# Schematic.net
KiCad netlist of a schematic drawn in Altium Designer
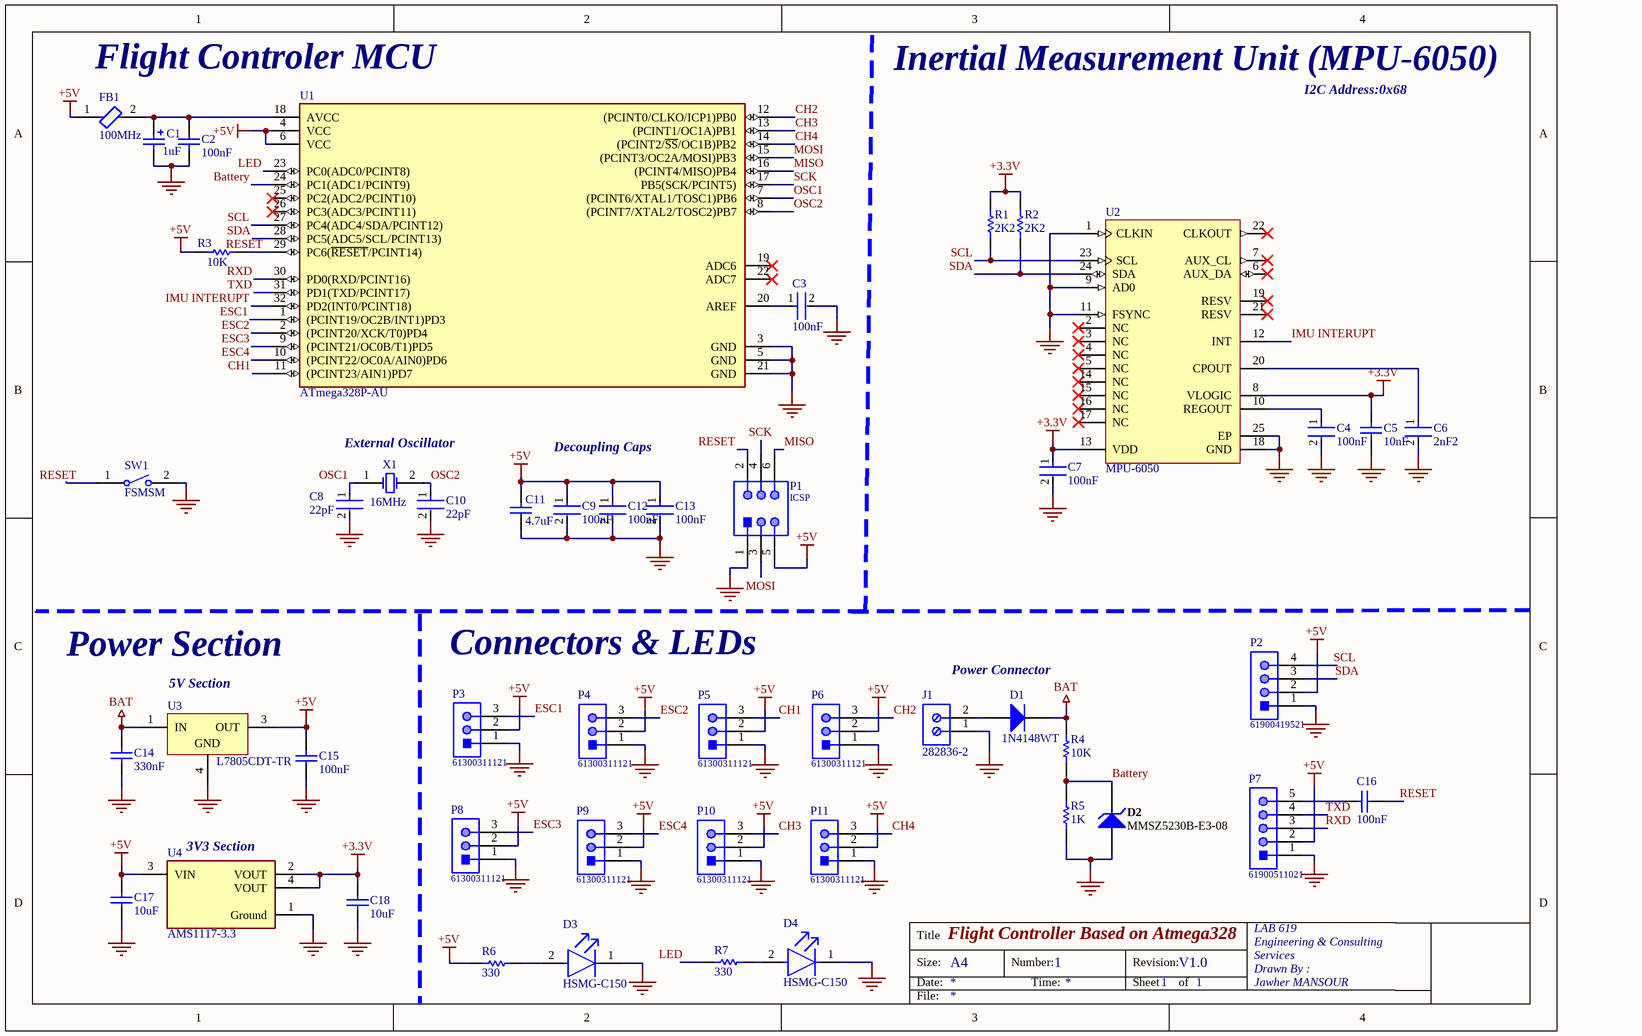
[diagram p0: Schematic.SchDoc]

(export (version "E")
  (design (tool "Eeschema 10.0.6"))
  (components
    (comp (ref "C1")
      (value "1uF")
      (footprint "C1206")
      (description "Polarized Capacitor (Axial)")
      (fields (field (name "PUBLISHER") "Altium Limited"))
      (libsource (lib "Miscellaneous Devices") (part "Cap Pol2"))
    )
    (comp (ref "C2")
      (value "100nF")
      (footprint "CAPC3216X95X55NL15T25")
      (description "Chip Capacitor, 0.1 uF, +/- 10%, 50 V, -55 to 125 degC, 1206 (3216 Metric), RoHS, Tape and Reel")
      (fields (field (name "MANUFACTURER") "Murata"))
      (libsource (lib "Altium Content Vault") (part "CAP-NP-2"))
    )
    (comp (ref "C3")
      (value "100nF")
      (footprint "FP-GRM21B-0_15-MFG")
      (description "Chip Multilayer Ceramic Capacitors for General Purpose, 0805, 22uF, X5R, 15%, 20%, 6.3V")
      (fields (field (name "VOLTAGE") "6.3V") (field (name "TOLERANCE") "20%"))
      (libsource (lib "Altium Content Vault") (part "b4654b650e69147ec39a6b967a45e02"))
    )
    (comp (ref "C4")
      (value "100nF")
      (footprint "FP-GRM188-0_1-e0_2_0_5-IPC_B")
      (description "Chip Multilayer Ceramic Capacitors for General Purpose, 0603, 0.10uF, X7R, 15%, 10%, 100V")
      (fields (field (name "VOLTAGE") "100V") (field (name "TOLERANCE") "10%"))
      (libsource (lib "Altium Content Vault") (part "11868f565c42a9108669ba33697ecf6"))
    )
    (comp (ref "C5")
      (value "10nF")
      (footprint "CAPC1608X90X35ML15T15")
      (fields
        (field (name "MANUFACTURER") "AVX Interconnect / Elco")
        (field (name "PART NUMBER") "0603ZC103MAT2A")
      )
      (libsource (lib "Altium Content Vault") (part "CAP"))
    )
    (comp (ref "C6")
      (value "2nF2")
      (footprint "FP-C0603C-CF-MFG")
      (description "CAP CER 2200PF 100V NP0 0603")
      (fields
        (field (name "OCTOPART") "https://octopart.com/c0603c222f1gactu-kemet-16902737")
        (field (name "MANUFACTURER PART NUMBER") "C0603C222F1GACTU")
      )
      (libsource (lib "Altium Content Vault") (part "b4654b650e69147ec39a6b967a45e02"))
    )
    (comp (ref "C7")
      (value "100nF")
      (footprint "FP-GRM188-0_1-e0_2_0_5-IPC_B")
      (description "Chip Multilayer Ceramic Capacitors for General Purpose, 0603, 0.10uF, X7R, 15%, 10%, 100V")
      (fields (field (name "VOLTAGE") "100V") (field (name "TOLERANCE") "10%"))
      (libsource (lib "Altium Content Vault") (part "11868f565c42a9108669ba33697ecf6"))
    )
    (comp (ref "C8")
      (value "22pF")
      (footprint "FP-C1206C-EB-MFG")
      (description "CAP CER 22PF 100V 5% NP0 1206")
      (fields
        (field (name "MANUFACTURER PART NUMBER") "C1206C220J1GACTU")
        (field (name "MANUFACTURER") "KEMET")
      )
      (libsource (lib "Altium Content Vault") (part "b4654b650e69147ec39a6b967a45e02"))
    )
    (comp (ref "C9")
      (value "100nF")
      (footprint "FP-GRM21B-0_15-MFG")
      (description "Chip Multilayer Ceramic Capacitors for General Purpose, 0805, 22uF, X5R, 15%, 20%, 6.3V")
      (fields (field (name "VOLTAGE") "6.3V") (field (name "TOLERANCE") "20%"))
      (libsource (lib "Altium Content Vault") (part "b4654b650e69147ec39a6b967a45e02"))
    )
    (comp (ref "C10")
      (value "22pF")
      (footprint "FP-C1206C-EB-MFG")
      (description "CAP CER 22PF 100V 5% NP0 1206")
      (fields
        (field (name "MANUFACTURER PART NUMBER") "C1206C220J1GACTU")
        (field (name "MANUFACTURER") "KEMET")
      )
      (libsource (lib "Altium Content Vault") (part "b4654b650e69147ec39a6b967a45e02"))
    )
    (comp (ref "C11")
      (value "4.7uF")
      (footprint "CAPC3216X95X55NL15T25")
      (description "Chip Capacitor, 0.1 uF, +/- 10%, 50 V, -55 to 125 degC, 1206 (3216 Metric), RoHS, Tape and Reel")
      (fields (field (name "MANUFACTURER") "Murata"))
      (libsource (lib "Altium Content Vault") (part "CAP-NP-2"))
    )
    (comp (ref "C12")
      (value "100nF")
      (footprint "FP-GRM21B-0_15-MFG")
      (description "Chip Multilayer Ceramic Capacitors for General Purpose, 0805, 22uF, X5R, 15%, 20%, 6.3V")
      (fields (field (name "VOLTAGE") "6.3V") (field (name "TOLERANCE") "20%"))
      (libsource (lib "Altium Content Vault") (part "b4654b650e69147ec39a6b967a45e02"))
    )
    (comp (ref "C13")
      (value "100nF")
      (footprint "FP-GRM21B-0_15-MFG")
      (description "Chip Multilayer Ceramic Capacitors for General Purpose, 0805, 22uF, X5R, 15%, 20%, 6.3V")
      (fields (field (name "VOLTAGE") "6.3V") (field (name "TOLERANCE") "20%"))
      (libsource (lib "Altium Content Vault") (part "b4654b650e69147ec39a6b967a45e02"))
    )
    (comp (ref "C14")
      (value "330nF")
      (footprint "CAPC3216X95X55NL15T25")
      (description "Chip Capacitor, 0.1 uF, +/- 10%, 50 V, -55 to 125 degC, 1206 (3216 Metric), RoHS, Tape and Reel")
      (fields (field (name "MANUFACTURER") "Murata"))
      (libsource (lib "Altium Content Vault") (part "CAP-NP-2"))
    )
    (comp (ref "C15")
      (value "100nF")
      (footprint "CAPC3216X95X55NL15T25")
      (description "Chip Capacitor, 0.1 uF, +/- 10%, 50 V, -55 to 125 degC, 1206 (3216 Metric), RoHS, Tape and Reel")
      (fields (field (name "MANUFACTURER") "Murata"))
      (libsource (lib "Altium Content Vault") (part "CAP-NP-2"))
    )
    (comp (ref "C16")
      (value "100nF")
      (footprint "CAPC3216X95X55NL15T25")
      (description "Chip Capacitor, 0.1 uF, +/- 10%, 50 V, -55 to 125 degC, 1206 (3216 Metric), RoHS, Tape and Reel")
      (fields (field (name "MANUFACTURER") "Murata"))
      (libsource (lib "Altium Content Vault") (part "CAP-NP-2"))
    )
    (comp (ref "C17")
      (value "10uF")
      (footprint "CAPC3216X95X55NL15T25")
      (description "Chip Capacitor, 0.1 uF, +/- 10%, 50 V, -55 to 125 degC, 1206 (3216 Metric), RoHS, Tape and Reel")
      (fields (field (name "MANUFACTURER") "Murata"))
      (libsource (lib "Altium Content Vault") (part "CAP-NP-2"))
    )
    (comp (ref "C18")
      (value "10uF")
      (footprint "CAPC3216X95X55NL15T25")
      (description "Chip Capacitor, 0.1 uF, +/- 10%, 50 V, -55 to 125 degC, 1206 (3216 Metric), RoHS, Tape and Reel")
      (fields (field (name "MANUFACTURER") "Murata"))
      (libsource (lib "Altium Content Vault") (part "CAP-NP-2"))
    )
    (comp (ref "D1")
      (value "1N4148WT")
      (footprint "FAIR-SOD-523F-2_V")
      (description "High Conductance Fast Switching Diode, 75 V, -55 to 150 degC, 2-Pin SOD523F, RoHS")
      (fields (field (name "MANUFACTURER") "Fairchild Semiconductor"))
      (libsource (lib "Altium Content Vault") (part "FAIR-D_K1A2-2"))
    )
    (comp (ref "D2")
      (value "MMSZ5230B-E3-08")
      (footprint "VISH-SOD-123-2_V")
      (description "Small Signal Zener Diode, 4.7 V +/- 5%, -55 to 155 degC, 2-Pin SOD-123, RoHS, Tape and Reel")
      (fields (field (name "MANUFACTURER") "Vishay Semiconductor") (field (name "TOLERANCE") "+/- 5%"))
      (libsource (lib "Altium Content Vault") (part "VISH-DZEN_A1K2-2"))
    )
    (comp (ref "D3")
      (value "HSMG-C150")
      (footprint "FP-HSMG-C150-MFG")
      (description "LED GREEN DIFFUSED 1206 SMD")
      (fields
        (field (name "MANUFACTURER") "Broadcom")
        (field (name "OCTOPART") "https://octopart.com/hsmg-c150-broadcom-71131304")
      )
      (libsource (lib "Altium Content Vault") (part "8706943c75ba83719d021d2fdc84c58"))
    )
    (comp (ref "D4")
      (value "HSMG-C150")
      (footprint "FP-HSMG-C150-MFG")
      (description "LED GREEN DIFFUSED 1206 SMD")
      (fields
        (field (name "MANUFACTURER") "Broadcom")
        (field (name "OCTOPART") "https://octopart.com/hsmg-c150-broadcom-71131304")
      )
      (libsource (lib "Altium Content Vault") (part "8706943c75ba83719d021d2fdc84c58"))
    )
    (comp (ref "FB1")
      (value "100MHz")
      (footprint "FP-BLM21-0_2-t0_85-e0_5-IPC_A")
      (description "FERRITE BEAD 120 OHM 0805 1LN")
      (fields (field (name "TOLERANCE") "25%"))
      (libsource (lib "Altium Content Vault") (part "5f30dd21d616792df468990f7003faa"))
    )
    (comp (ref "J1")
      (value "282836-2")
      (footprint "TECO-282836-2_V")
      (description "Female Header, Pitch 5 mm, 1 x 2 Position, Height 10 mm, Tail Length 3.5 mm, Rohs, Bulk")
      (fields (field (name "VOLTAGE") "300V") (field (name "MANUFACTURER") "TE Connectivity"))
      (libsource (lib "Altium Content Vault") (part "CN-1P-F-TB2"))
    )
    (comp (ref "P1")
      (value "ICSP")
      (footprint "61300621121")
      (description "THT Vertical Pin Header WR-PHD, Pitch 2.54 mm, Dual Row, 6 pins")
      (fields
        (field (name "MANUFACTURER") "Wurth Elektronik")
        (field (name "PART NUMBER") "61300621121")
        (field (name "PUBLISHER") "WurthElektronik")
      )
      (libsource (lib "Altium Content Vault") (part "WE-CN-2P-M-R6"))
    )
    (comp (ref "P2")
      (value "61900419521")
      (footprint "61900419521")
      (description "Male Top Locking Header WR-WTB, THT, Right Angled, pitch 2.54 mm, 1 x 4 position")
      (fields (field (name "MANUFACTURER") "Wurth Elektronik") (field (name "PUBLISHER") "WurthElektronik"))
      (libsource (lib "Altium Content Vault") (part "WE-CN-1P-M-R4"))
    )
    (comp (ref "P3")
      (value "61300311121")
      (footprint "61300311121")
      (description "THT Vertical Pin Header WR-PHD, Pitch 2.54 mm, Single Row, 3 pins")
      (fields (field (name "MANUFACTURER") "Wurth Elektronik") (field (name "PUBLISHER") "WurthElektronik"))
      (libsource (lib "Altium Content Vault") (part "WE-CN-1P-M-R3"))
    )
    (comp (ref "P4")
      (value "61300311121")
      (footprint "61300311121")
      (description "THT Vertical Pin Header WR-PHD, Pitch 2.54 mm, Single Row, 3 pins")
      (fields (field (name "MANUFACTURER") "Wurth Elektronik") (field (name "PUBLISHER") "WurthElektronik"))
      (libsource (lib "Altium Content Vault") (part "WE-CN-1P-M-R3"))
    )
    (comp (ref "P5")
      (value "61300311121")
      (footprint "61300311121")
      (description "THT Vertical Pin Header WR-PHD, Pitch 2.54 mm, Single Row, 3 pins")
      (fields (field (name "MANUFACTURER") "Wurth Elektronik") (field (name "PUBLISHER") "WurthElektronik"))
      (libsource (lib "Altium Content Vault") (part "WE-CN-1P-M-R3"))
    )
    (comp (ref "P6")
      (value "61300311121")
      (footprint "61300311121")
      (description "THT Vertical Pin Header WR-PHD, Pitch 2.54 mm, Single Row, 3 pins")
      (fields (field (name "MANUFACTURER") "Wurth Elektronik") (field (name "PUBLISHER") "WurthElektronik"))
      (libsource (lib "Altium Content Vault") (part "WE-CN-1P-M-R3"))
    )
    (comp (ref "P7")
      (value "61900511021")
      (footprint "61900511021")
      (description "Male Bottom Locking Header WR-WTB, THT, Right Angled, pitch 2.54 mm, 1 x 5 position")
      (fields (field (name "MANUFACTURER") "Wurth Elektronik") (field (name "PUBLISHER") "WurthElektronik"))
      (libsource (lib "Altium Content Vault") (part "WE-CN-1P-M-R5"))
    )
    (comp (ref "P8")
      (value "61300311121")
      (footprint "61300311121")
      (description "THT Vertical Pin Header WR-PHD, Pitch 2.54 mm, Single Row, 3 pins")
      (fields (field (name "MANUFACTURER") "Wurth Elektronik") (field (name "PUBLISHER") "WurthElektronik"))
      (libsource (lib "Altium Content Vault") (part "WE-CN-1P-M-R3"))
    )
    (comp (ref "P9")
      (value "61300311121")
      (footprint "61300311121")
      (description "THT Vertical Pin Header WR-PHD, Pitch 2.54 mm, Single Row, 3 pins")
      (fields (field (name "MANUFACTURER") "Wurth Elektronik") (field (name "PUBLISHER") "WurthElektronik"))
      (libsource (lib "Altium Content Vault") (part "WE-CN-1P-M-R3"))
    )
    (comp (ref "P10")
      (value "61300311121")
      (footprint "61300311121")
      (description "THT Vertical Pin Header WR-PHD, Pitch 2.54 mm, Single Row, 3 pins")
      (fields (field (name "MANUFACTURER") "Wurth Elektronik") (field (name "PUBLISHER") "WurthElektronik"))
      (libsource (lib "Altium Content Vault") (part "WE-CN-1P-M-R3"))
    )
    (comp (ref "P11")
      (value "61300311121")
      (footprint "61300311121")
      (description "THT Vertical Pin Header WR-PHD, Pitch 2.54 mm, Single Row, 3 pins")
      (fields (field (name "MANUFACTURER") "Wurth Elektronik") (field (name "PUBLISHER") "WurthElektronik"))
      (libsource (lib "Altium Content Vault") (part "WE-CN-1P-M-R3"))
    )
    (comp (ref "R1")
      (value "2K2")
      (footprint "RESC3116X65X40ML10T20")
      (description "Chip Resistor, 10 KOhm, +/- 1%, 0.25 W, -55 to 155 degC, 1206 (3216 Metric), RoHS, Tape and Reel")
      (fields (field (name "TOLERANCE") "1%") (field (name "MANUFACTURER") "Yageo"))
      (libsource (lib "Altium Content Vault") (part "RES-2"))
    )
    (comp (ref "R2")
      (value "2K2")
      (footprint "RESC3116X65X40ML10T20")
      (description "Chip Resistor, 10 KOhm, +/- 1%, 0.25 W, -55 to 155 degC, 1206 (3216 Metric), RoHS, Tape and Reel")
      (fields (field (name "TOLERANCE") "1%") (field (name "MANUFACTURER") "Yageo"))
      (libsource (lib "Altium Content Vault") (part "RES-2"))
    )
    (comp (ref "R3")
      (value "10K")
      (footprint "RESC3116X65X40ML10T20")
      (description "Chip Resistor, 10 KOhm, +/- 1%, 0.25 W, -55 to 155 degC, 1206 (3216 Metric), RoHS, Tape and Reel")
      (fields (field (name "TOLERANCE") "1%") (field (name "MANUFACTURER") "Yageo"))
      (libsource (lib "Altium Content Vault") (part "RES-2"))
    )
    (comp (ref "R4")
      (value "10K")
      (footprint "RESC3116X65X40ML10T20")
      (description "Chip Resistor, 10 KOhm, +/- 1%, 0.25 W, -55 to 155 degC, 1206 (3216 Metric), RoHS, Tape and Reel")
      (fields (field (name "TOLERANCE") "1%") (field (name "MANUFACTURER") "Yageo"))
      (libsource (lib "Altium Content Vault") (part "RES-2"))
    )
    (comp (ref "R5")
      (value "1K")
      (footprint "RESC3116X65X40ML10T20")
      (description "Chip Resistor, 10 KOhm, +/- 1%, 0.25 W, -55 to 155 degC, 1206 (3216 Metric), RoHS, Tape and Reel")
      (fields (field (name "TOLERANCE") "1%") (field (name "MANUFACTURER") "Yageo"))
      (libsource (lib "Altium Content Vault") (part "RES-2"))
    )
    (comp (ref "R6")
      (value "330")
      (footprint "RESC3116X65X40ML10T20")
      (description "Chip Resistor, 10 KOhm, +/- 1%, 0.25 W, -55 to 155 degC, 1206 (3216 Metric), RoHS, Tape and Reel")
      (fields (field (name "TOLERANCE") "1%") (field (name "MANUFACTURER") "Yageo"))
      (libsource (lib "Altium Content Vault") (part "RES-2"))
    )
    (comp (ref "R7")
      (value "330")
      (footprint "RESC3116X65X40ML10T20")
      (description "Chip Resistor, 10 KOhm, +/- 1%, 0.25 W, -55 to 155 degC, 1206 (3216 Metric), RoHS, Tape and Reel")
      (fields (field (name "TOLERANCE") "1%") (field (name "MANUFACTURER") "Yageo"))
      (libsource (lib "Altium Content Vault") (part "RES-2"))
    )
    (comp (ref "SW1")
      (value "FSMSM")
      (footprint "TECO-FSMSM-2_V")
      (description "FSMSM Push Button Switch, 50 mA, -35 to 85 degC, 2-Pin SMD, RoHS, Bulk")
      (fields (field (name "MANUFACTURER") "TE Connectivity"))
      (libsource (lib "Altium Content Vault") (part "SW-SPST-2_C"))
    )
    (comp (ref "U1")
      (value "ATmega328P-AU")
      (footprint "FP-32A-MFG")
      (description "IC MCU 8BIT 32KB FLASH 32TQFP")
      (fields
        (field (name "MANUFACTURER") "Microchip")
        (field (name "OCTOPART") "https://octopart.com/atmega328p-au-microchip-77760215")
      )
      (libsource (lib "Altium Content Vault") (part "f5fbdcb2c0c597ef7d3dd1575aef21a"))
    )
    (comp (ref "U2")
      (value "MPU-6050")
      (footprint "IS-QFN-24_V")
      (fields (field (name "MANUFACTURER") "InvenSense"))
      (libsource (lib "Altium Content Vault") (part "IS-MPU-6050-QFN-24"))
    )
    (comp (ref "U3")
      (value "L7805CDT-TR")
      (footprint "TO-252_N")
      (description "Positive Voltage Regulator, 3-Pin DPAK, Tape and Reel")
      (libsource (lib "Altium Content Vault") (part "PM-REG-L4940-SOT3"))
    )
    (comp (ref "U4")
      (value "AMS1117-3.3")
      (footprint "FP-AMS1117-IPC_C")
      (description "LDO Voltage Regulators 1A, 3.3V")
      (fields
        (field (name "OCTOPART") "https://octopart.com/ams1117-3.3-advanced+monolithic+systems-25899300")
        (field (name "MANUFACTURER") "Advanced Monolithic Systems")
      )
      (libsource (lib "Altium Content Vault") (part "8bdbb5f8e77002000e30dd2845d0354"))
    )
    (comp (ref "X1")
      (value "16MHz")
      (footprint "FOX-FOXSDLF160-20_V")
      (libsource (lib "Altium Content Vault") (part "XTAL_1-2-2"))
    )
  )
  (nets
    (net (code "1") (name "+3.3V") (class "Default")
      (node (ref "C18") (pin "2") (pinfunction "2_2") (pintype "passive"))
      (node (ref "C5") (pin "2") (pinfunction "2_2") (pintype "passive"))
      (node (ref "C7") (pin "1") (pinfunction "1_1") (pintype "passive"))
      (node (ref "R1") (pin "1") (pinfunction "1_1") (pintype "passive"))
      (node (ref "R2") (pin "1") (pinfunction "1_1") (pintype "passive"))
      (node (ref "U2") (pin "13") (pinfunction "VDD_13") (pintype "power_in"))
      (node (ref "U2") (pin "8") (pinfunction "VLOGIC_8") (pintype "power_in"))
      (node (ref "U4") (pin "2") (pinfunction "VOUT_2") (pintype "passive"))
      (node (ref "U4") (pin "4") (pinfunction "VOUT_4") (pintype "passive"))
    )
    (net (code "2") (name "+5V") (class "Default")
      (node (ref "C11") (pin "2") (pinfunction "2_2") (pintype "passive"))
      (node (ref "C12") (pin "1") (pinfunction "1_1") (pintype "passive"))
      (node (ref "C13") (pin "1") (pinfunction "1_1") (pintype "passive"))
      (node (ref "C15") (pin "2") (pinfunction "2_2") (pintype "passive"))
      (node (ref "C17") (pin "2") (pinfunction "2_2") (pintype "passive"))
      (node (ref "C9") (pin "1") (pinfunction "1_1") (pintype "passive"))
      (node (ref "FB1") (pin "1") (pinfunction "1_1") (pintype "passive"))
      (node (ref "P1") (pin "5") (pinfunction "5_5") (pintype "passive"))
      (node (ref "P10") (pin "2") (pinfunction "2_2") (pintype "passive"))
      (node (ref "P11") (pin "2") (pinfunction "2_2") (pintype "passive"))
      (node (ref "P2") (pin "2") (pinfunction "2_2") (pintype "passive"))
      (node (ref "P3") (pin "2") (pinfunction "2_2") (pintype "passive"))
      (node (ref "P4") (pin "2") (pinfunction "2_2") (pintype "passive"))
      (node (ref "P5") (pin "2") (pinfunction "2_2") (pintype "passive"))
      (node (ref "P6") (pin "2") (pinfunction "2_2") (pintype "passive"))
      (node (ref "P7") (pin "2") (pinfunction "2_2") (pintype "passive"))
      (node (ref "P8") (pin "2") (pinfunction "2_2") (pintype "passive"))
      (node (ref "P9") (pin "2") (pinfunction "2_2") (pintype "passive"))
      (node (ref "R3") (pin "1") (pinfunction "1_1") (pintype "passive"))
      (node (ref "R6") (pin "2") (pinfunction "2_2") (pintype "passive"))
      (node (ref "U1") (pin "4") (pinfunction "VCC_4") (pintype "power_in"))
      (node (ref "U1") (pin "6") (pinfunction "VCC_6") (pintype "power_in"))
      (node (ref "U3") (pin "3") (pinfunction "OUT_3") (pintype "power_in"))
      (node (ref "U4") (pin "3") (pinfunction "VIN_3") (pintype "power_in"))
    )
    (net (code "3") (name "/Battery") (class "Default")
      (node (ref "D2") (pin "2") (pinfunction "K_2") (pintype "passive"))
      (node (ref "R4") (pin "1") (pinfunction "1_1") (pintype "passive"))
      (node (ref "R5") (pin "2") (pinfunction "2_2") (pintype "passive"))
      (node (ref "U1") (pin "24") (pinfunction "PC1(ADC1/PCINT9)_24") (pintype "bidirectional"))
    )
    (net (code "4") (name "/CH1") (class "Default")
      (node (ref "P5") (pin "3") (pinfunction "3_3") (pintype "passive"))
      (node (ref "U1") (pin "11") (pinfunction "(PCINT23/AIN1)PD7_11") (pintype "bidirectional"))
    )
    (net (code "5") (name "/CH2") (class "Default")
      (node (ref "P6") (pin "3") (pinfunction "3_3") (pintype "passive"))
      (node (ref "U1") (pin "12") (pinfunction "(PCINT0/CLKO/ICP1)PB0_12") (pintype "bidirectional"))
    )
    (net (code "6") (name "/CH3") (class "Default")
      (node (ref "P10") (pin "3") (pinfunction "3_3") (pintype "passive"))
      (node (ref "U1") (pin "13") (pinfunction "(PCINT1/OC1A)PB1_13") (pintype "bidirectional"))
    )
    (net (code "7") (name "/CH4") (class "Default")
      (node (ref "P11") (pin "3") (pinfunction "3_3") (pintype "passive"))
      (node (ref "U1") (pin "14") (pinfunction "(PCINT2/~{SS}/OC1B)PB2_14") (pintype "bidirectional"))
    )
    (net (code "8") (name "/ESC1") (class "Default")
      (node (ref "P3") (pin "3") (pinfunction "3_3") (pintype "passive"))
      (node (ref "U1") (pin "1") (pinfunction "(PCINT19/OC2B/INT1)PD3_1") (pintype "bidirectional"))
    )
    (net (code "9") (name "/ESC2") (class "Default")
      (node (ref "P4") (pin "3") (pinfunction "3_3") (pintype "passive"))
      (node (ref "U1") (pin "2") (pinfunction "(PCINT20/XCK/T0)PD4_2") (pintype "bidirectional"))
    )
    (net (code "10") (name "/ESC3") (class "Default")
      (node (ref "P8") (pin "3") (pinfunction "3_3") (pintype "passive"))
      (node (ref "U1") (pin "9") (pinfunction "(PCINT21/OC0B/T1)PD5_9") (pintype "bidirectional"))
    )
    (net (code "11") (name "/ESC4") (class "Default")
      (node (ref "P9") (pin "3") (pinfunction "3_3") (pintype "passive"))
      (node (ref "U1") (pin "10") (pinfunction "(PCINT22/OC0A/AIN0)PD6_10") (pintype "bidirectional"))
    )
    (net (code "12") (name "/IMU INTERUPT") (class "Default")
      (node (ref "U1") (pin "32") (pinfunction "PD2(INT0/PCINT18)_32") (pintype "bidirectional"))
      (node (ref "U2") (pin "12") (pinfunction "INT_12") (pintype "open_collector"))
    )
    (net (code "13") (name "/LED") (class "Default")
      (node (ref "R7") (pin "1") (pinfunction "1_1") (pintype "passive"))
      (node (ref "U1") (pin "23") (pinfunction "PC0(ADC0/PCINT8)_23") (pintype "bidirectional"))
    )
    (net (code "14") (name "/MISO") (class "Default")
      (node (ref "P1") (pin "6") (pinfunction "6_6") (pintype "passive"))
      (node (ref "U1") (pin "16") (pinfunction "(PCINT4/MISO)PB4_16") (pintype "bidirectional"))
    )
    (net (code "15") (name "/MOSI") (class "Default")
      (node (ref "P1") (pin "3") (pinfunction "3_3") (pintype "passive"))
      (node (ref "U1") (pin "15") (pinfunction "(PCINT3/OC2A/MOSI)PB3_15") (pintype "bidirectional"))
    )
    (net (code "16") (name "/OSC1") (class "Default")
      (node (ref "C8") (pin "1") (pinfunction "1_1") (pintype "passive"))
      (node (ref "U1") (pin "7") (pinfunction "(PCINT6/XTAL1/TOSC1)PB6_7") (pintype "bidirectional"))
      (node (ref "X1") (pin "1") (pinfunction "X1_1") (pintype "passive"))
    )
    (net (code "17") (name "/OSC2") (class "Default")
      (node (ref "C10") (pin "1") (pinfunction "1_1") (pintype "passive"))
      (node (ref "U1") (pin "8") (pinfunction "(PCINT7/XTAL2/TOSC2)PB7_8") (pintype "bidirectional"))
      (node (ref "X1") (pin "2") (pinfunction "X2_2") (pintype "passive"))
    )
    (net (code "18") (name "/RESET") (class "Default")
      (node (ref "C16") (pin "1") (pinfunction "1_1") (pintype "passive"))
      (node (ref "P1") (pin "2") (pinfunction "2_2") (pintype "passive"))
      (node (ref "R3") (pin "2") (pinfunction "2_2") (pintype "passive"))
      (node (ref "SW1") (pin "1") (pinfunction "1_1") (pintype "passive"))
      (node (ref "U1") (pin "29") (pinfunction "PC6(~{RESET}/PCINT14)_29") (pintype "bidirectional"))
    )
    (net (code "19") (name "/RXD") (class "Default")
      (node (ref "P7") (pin "3") (pinfunction "3_3") (pintype "passive"))
      (node (ref "U1") (pin "30") (pinfunction "PD0(RXD/PCINT16)_30") (pintype "bidirectional"))
    )
    (net (code "20") (name "/SCK") (class "Default")
      (node (ref "P1") (pin "4") (pinfunction "4_4") (pintype "passive"))
      (node (ref "U1") (pin "17") (pinfunction "PB5(SCK/PCINT5)_17") (pintype "bidirectional"))
    )
    (net (code "21") (name "/SCL") (class "Default")
      (node (ref "P2") (pin "4") (pinfunction "4_4") (pintype "passive"))
      (node (ref "R1") (pin "2") (pinfunction "2_2") (pintype "passive"))
      (node (ref "U1") (pin "27") (pinfunction "PC4(ADC4/SDA/PCINT12)_27") (pintype "bidirectional"))
      (node (ref "U2") (pin "23") (pinfunction "SCL_23") (pintype "input"))
    )
    (net (code "22") (name "/SDA") (class "Default")
      (node (ref "P2") (pin "3") (pinfunction "3_3") (pintype "passive"))
      (node (ref "R2") (pin "2") (pinfunction "2_2") (pintype "passive"))
      (node (ref "U1") (pin "28") (pinfunction "PC5(ADC5/SCL/PCINT13)_28") (pintype "bidirectional"))
      (node (ref "U2") (pin "24") (pinfunction "SDA_24") (pintype "bidirectional"))
    )
    (net (code "23") (name "/TXD") (class "Default")
      (node (ref "P7") (pin "4") (pinfunction "4_4") (pintype "passive"))
      (node (ref "U1") (pin "31") (pinfunction "PD1(TXD/PCINT17)_31") (pintype "bidirectional"))
    )
    (net (code "24") (name "BAT") (class "Default")
      (node (ref "C14") (pin "2") (pinfunction "2_2") (pintype "passive"))
      (node (ref "D1") (pin "1") (pinfunction "K_1") (pintype "passive"))
      (node (ref "R4") (pin "2") (pinfunction "2_2") (pintype "passive"))
      (node (ref "U3") (pin "1") (pinfunction "IN_1") (pintype "power_in"))
    )
    (net (code "25") (name "GND") (class "Default")
      (node (ref "C1") (pin "2") (pinfunction "2_2") (pintype "passive"))
      (node (ref "C10") (pin "2") (pinfunction "2_2") (pintype "passive"))
      (node (ref "C11") (pin "1") (pinfunction "1_1") (pintype "passive"))
      (node (ref "C12") (pin "2") (pinfunction "2_2") (pintype "passive"))
      (node (ref "C13") (pin "2") (pinfunction "2_2") (pintype "passive"))
      (node (ref "C14") (pin "1") (pinfunction "1_1") (pintype "passive"))
      (node (ref "C15") (pin "1") (pinfunction "1_1") (pintype "passive"))
      (node (ref "C17") (pin "1") (pinfunction "1_1") (pintype "passive"))
      (node (ref "C18") (pin "1") (pinfunction "1_1") (pintype "passive"))
      (node (ref "C2") (pin "1") (pinfunction "1_1") (pintype "passive"))
      (node (ref "C3") (pin "2") (pinfunction "2_2") (pintype "passive"))
      (node (ref "C4") (pin "2") (pinfunction "2_2") (pintype "passive"))
      (node (ref "C5") (pin "1") (pinfunction "1_1") (pintype "passive"))
      (node (ref "C6") (pin "2") (pinfunction "2_2") (pintype "passive"))
      (node (ref "C7") (pin "2") (pinfunction "2_2") (pintype "passive"))
      (node (ref "C8") (pin "2") (pinfunction "2_2") (pintype "passive"))
      (node (ref "C9") (pin "2") (pinfunction "2_2") (pintype "passive"))
      (node (ref "D2") (pin "1") (pinfunction "A_1") (pintype "passive"))
      (node (ref "D3") (pin "1") (pinfunction "C_1") (pintype "passive"))
      (node (ref "D4") (pin "1") (pinfunction "C_1") (pintype "passive"))
      (node (ref "J1") (pin "1") (pinfunction "1_1") (pintype "passive"))
      (node (ref "P1") (pin "1") (pinfunction "1_1") (pintype "passive"))
      (node (ref "P10") (pin "1") (pinfunction "1_1") (pintype "passive"))
      (node (ref "P11") (pin "1") (pinfunction "1_1") (pintype "passive"))
      (node (ref "P2") (pin "1") (pinfunction "1_1") (pintype "passive"))
      (node (ref "P3") (pin "1") (pinfunction "1_1") (pintype "passive"))
      (node (ref "P4") (pin "1") (pinfunction "1_1") (pintype "passive"))
      (node (ref "P5") (pin "1") (pinfunction "1_1") (pintype "passive"))
      (node (ref "P6") (pin "1") (pinfunction "1_1") (pintype "passive"))
      (node (ref "P7") (pin "1") (pinfunction "1_1") (pintype "passive"))
      (node (ref "P8") (pin "1") (pinfunction "1_1") (pintype "passive"))
      (node (ref "P9") (pin "1") (pinfunction "1_1") (pintype "passive"))
      (node (ref "R5") (pin "1") (pinfunction "1_1") (pintype "passive"))
      (node (ref "SW1") (pin "2") (pinfunction "2_2") (pintype "passive"))
      (node (ref "U1") (pin "21") (pinfunction "GND_21") (pintype "power_in"))
      (node (ref "U1") (pin "3") (pinfunction "GND_3") (pintype "power_in"))
      (node (ref "U1") (pin "5") (pinfunction "GND_5") (pintype "power_in"))
      (node (ref "U2") (pin "1") (pinfunction "CLKIN_1") (pintype "input"))
      (node (ref "U2") (pin "11") (pinfunction "FSYNC_11") (pintype "input"))
      (node (ref "U2") (pin "18") (pinfunction "GND_18") (pintype "power_in"))
      (node (ref "U2") (pin "25") (pinfunction "EP_25") (pintype "power_in"))
      (node (ref "U2") (pin "9") (pinfunction "AD0_9") (pintype "input"))
      (node (ref "U3") (pin "4") (pinfunction "GND_4") (pintype "power_in"))
      (node (ref "U4") (pin "1") (pinfunction "Ground_1") (pintype "power_in"))
    )
    (net (code "26") (name "Net-(C16-Pad2)") (class "Default")
      (node (ref "C16") (pin "2") (pinfunction "2_2") (pintype "passive"))
      (node (ref "P7") (pin "5") (pinfunction "5_5") (pintype "passive"))
    )
    (net (code "27") (name "Net-(D1-A)") (class "Default")
      (node (ref "D1") (pin "2") (pinfunction "A_2") (pintype "passive"))
      (node (ref "J1") (pin "2") (pinfunction "2_2") (pintype "passive"))
    )
    (net (code "28") (name "Net-(D3-A)") (class "Default")
      (node (ref "D3") (pin "2") (pinfunction "A_2") (pintype "passive"))
      (node (ref "R6") (pin "1") (pinfunction "1_1") (pintype "passive"))
    )
    (net (code "29") (name "Net-(D4-A)") (class "Default")
      (node (ref "D4") (pin "2") (pinfunction "A_2") (pintype "passive"))
      (node (ref "R7") (pin "2") (pinfunction "2_2") (pintype "passive"))
    )
    (net (code "30") (name "Net-(U1-AREF)") (class "Default")
      (node (ref "C3") (pin "1") (pinfunction "1_1") (pintype "passive"))
      (node (ref "U1") (pin "20") (pinfunction "AREF_20") (pintype "passive"))
    )
    (net (code "31") (name "Net-(U1-AVCC)") (class "Default")
      (node (ref "C1") (pin "1") (pinfunction "1_1") (pintype "passive"))
      (node (ref "C2") (pin "2") (pinfunction "2_2") (pintype "passive"))
      (node (ref "FB1") (pin "2") (pinfunction "2_2") (pintype "passive"))
      (node (ref "U1") (pin "18") (pinfunction "AVCC_18") (pintype "power_in"))
    )
    (net (code "32") (name "Net-(U2-CPOUT)") (class "Default")
      (node (ref "C6") (pin "1") (pinfunction "1_1") (pintype "passive"))
      (node (ref "U2") (pin "20") (pinfunction "CPOUT_20") (pintype "passive"))
    )
    (net (code "33") (name "Net-(U2-REGOUT)") (class "Default")
      (node (ref "C4") (pin "1") (pinfunction "1_1") (pintype "passive"))
      (node (ref "U2") (pin "10") (pinfunction "REGOUT_10") (pintype "passive"))
    )
    (net (code "34") (name "unconnected-(U1-ADC6-Pad19)") (class "Default")
      (node (ref "U1") (pin "19") (pinfunction "ADC6_19") (pintype "power_in+no_connect"))
    )
    (net (code "35") (name "unconnected-(U1-ADC7-Pad22)") (class "Default")
      (node (ref "U1") (pin "22") (pinfunction "ADC7_22") (pintype "passive+no_connect"))
    )
    (net (code "36") (name "unconnected-(U1-PC2(ADC2{slash}PCINT10)-Pad25)") (class "Default")
      (node (ref "U1") (pin "25") (pinfunction "PC2(ADC2/PCINT10)_25") (pintype "bidirectional+no_connect"))
    )
    (net (code "37") (name "unconnected-(U1-PC3(ADC3{slash}PCINT11)-Pad26)") (class "Default")
      (node (ref "U1") (pin "26") (pinfunction "PC3(ADC3/PCINT11)_26") (pintype "bidirectional+no_connect"))
    )
    (net (code "38") (name "unconnected-(U2-AUX_CL-Pad7)") (class "Default")
      (node (ref "U2") (pin "7") (pinfunction "AUX_CL_7") (pintype "output+no_connect"))
    )
    (net (code "39") (name "unconnected-(U2-AUX_DA-Pad6)") (class "Default")
      (node (ref "U2") (pin "6") (pinfunction "AUX_DA_6") (pintype "bidirectional+no_connect"))
    )
    (net (code "40") (name "unconnected-(U2-CLKOUT-Pad22)") (class "Default")
      (node (ref "U2") (pin "22") (pinfunction "CLKOUT_22") (pintype "output+no_connect"))
    )
    (net (code "41") (name "unconnected-(U2-NC-Pad2)") (class "Default")
      (node (ref "U2") (pin "2") (pinfunction "NC_2") (pintype "passive+no_connect"))
    )
    (net (code "42") (name "unconnected-(U2-NC-Pad3)") (class "Default")
      (node (ref "U2") (pin "3") (pinfunction "NC_3") (pintype "passive+no_connect"))
    )
    (net (code "43") (name "unconnected-(U2-NC-Pad4)") (class "Default")
      (node (ref "U2") (pin "4") (pinfunction "NC_4") (pintype "passive+no_connect"))
    )
    (net (code "44") (name "unconnected-(U2-NC-Pad5)") (class "Default")
      (node (ref "U2") (pin "5") (pinfunction "NC_5") (pintype "passive+no_connect"))
    )
    (net (code "45") (name "unconnected-(U2-NC-Pad14)") (class "Default")
      (node (ref "U2") (pin "14") (pinfunction "NC_14") (pintype "passive+no_connect"))
    )
    (net (code "46") (name "unconnected-(U2-NC-Pad15)") (class "Default")
      (node (ref "U2") (pin "15") (pinfunction "NC_15") (pintype "passive+no_connect"))
    )
    (net (code "47") (name "unconnected-(U2-NC-Pad16)") (class "Default")
      (node (ref "U2") (pin "16") (pinfunction "NC_16") (pintype "passive+no_connect"))
    )
    (net (code "48") (name "unconnected-(U2-NC-Pad17)") (class "Default")
      (node (ref "U2") (pin "17") (pinfunction "NC_17") (pintype "passive+no_connect"))
    )
    (net (code "49") (name "unconnected-(U2-RESV-Pad19)") (class "Default")
      (node (ref "U2") (pin "19") (pinfunction "RESV_19") (pintype "passive+no_connect"))
    )
    (net (code "50") (name "unconnected-(U2-RESV-Pad21)") (class "Default")
      (node (ref "U2") (pin "21") (pinfunction "RESV_21") (pintype "passive+no_connect"))
    )
  )
)
